# VREG_AOZ1021AI_3V3_3A.net
KiCad netlist of a schematic drawn in Altium Designer
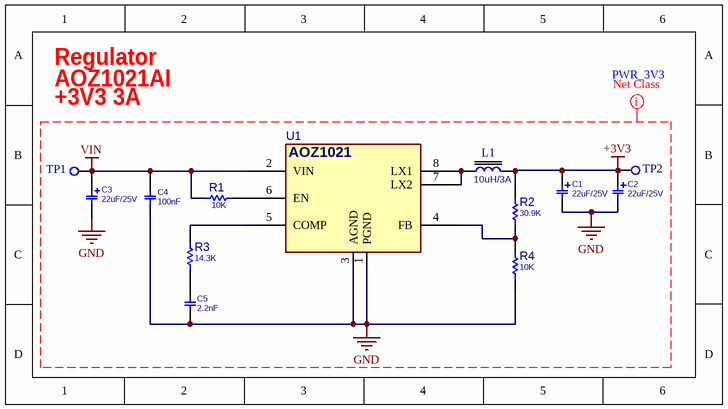
[diagram p0: VREG AOZ1021AI +3V3 3A.SchDoc]

(export (version "E")
  (design (tool "Eeschema 10.0.6"))
  (components
    (comp (ref "C1")
      (value "22uF/25V")
      (footprint "C_TN_A")
      (description "CAP, SMD, TAN")
      (libsource (lib "Passive") (part "CAP_SMD_TAN"))
    )
    (comp (ref "C2")
      (value "22uF/25V")
      (footprint "C_TN_A")
      (description "CAP, SMD, TAN")
      (libsource (lib "Passive") (part "CAP_SMD_TAN"))
    )
    (comp (ref "C3")
      (value "22uF/25V")
      (footprint "C_TN_A")
      (description "CAP, SMD, TAN")
      (libsource (lib "Passive") (part "CAP_SMD_TAN"))
    )
    (comp (ref "C4")
      (value "100nF")
      (footprint "C0603S")
      (description "CAP, SMD, MLCC")
      (fields (field (name "MANF_P#") "MANF_PART#") (field (name "MANF") "Murata"))
      (libsource (lib "Passive") (part "CAP_SMD_MLCC"))
    )
    (comp (ref "C5")
      (value "2.2nF")
      (footprint "C0603S")
      (description "CAP, SMD, MLCC")
      (fields (field (name "MANF_P#") "MANF_PART#") (field (name "MANF") "Murata"))
      (libsource (lib "Passive") (part "CAP_SMD_MLCC"))
    )
    (comp (ref "L1")
      (value "10uH/3A")
      (footprint "L_8X8")
      (description "IND, PWR, SMD")
      (libsource (lib "Passive") (part "INDPWR_SMD"))
    )
    (comp (ref "R1")
      (value "10K")
      (footprint "R0603S")
      (description "RES, SMD")
      (fields (field (name "MANF_P#") "RK73H1ETTP4701F") (field (name "MANF") "KOA SPEER"))
      (libsource (lib "Passive") (part "RES_SMD"))
    )
    (comp (ref "R2")
      (value "30.9K")
      (footprint "R0603S")
      (description "RES, SMD")
      (fields (field (name "MANF_P#") "RK73H1ETTP4701F") (field (name "MANF") "KOA SPEER"))
      (libsource (lib "Passive") (part "RES_SMD"))
    )
    (comp (ref "R3")
      (value "14.3K")
      (footprint "R0603S")
      (description "RES, SMD")
      (fields (field (name "MANF_P#") "RK73H1ETTP4701F") (field (name "MANF") "KOA SPEER"))
      (libsource (lib "Passive") (part "RES_SMD"))
    )
    (comp (ref "R4")
      (value "10K")
      (footprint "R0603S")
      (description "RES, SMD")
      (fields (field (name "MANF_P#") "RK73H1ETTP4701F") (field (name "MANF") "KOA SPEER"))
      (libsource (lib "Passive") (part "RES_SMD"))
    )
    (comp (ref "TP1")
      (value "Test Point")
      (footprint "TPSMD_C1")
      (libsource (lib "PW Components") (part "Test Point"))
    )
    (comp (ref "TP2")
      (value "Test Point")
      (footprint "TPSMD_C1")
      (libsource (lib "PW Components") (part "Test Point"))
    )
    (comp (ref "U1")
      (value "AOZ1021AI")
      (footprint "SO_8")
      (description "REG, Switching, Buck, 3A, ADJ, 500KHz, 4.5~16VIN, SO-8")
      (fields (field (name "MANF") "AOSMD"))
      (libsource (lib "PW Components") (part "VREG_AOZ1021AI_SO8"))
    )
  )
  (nets
    (net (code "1") (name "+3V3") (class "Default")
      (node (ref "C1") (pin "1") (pinfunction "1_1") (pintype "passive"))
      (node (ref "C2") (pin "1") (pinfunction "1_1") (pintype "passive"))
      (node (ref "L1") (pin "2") (pinfunction "2_2") (pintype "passive"))
      (node (ref "R2") (pin "1") (pinfunction "1_1") (pintype "passive"))
      (node (ref "TP2") (pin "1") (pinfunction "TP_1") (pintype "passive"))
    )
    (net (code "2") (name "GND") (class "Default")
      (node (ref "C1") (pin "2") (pinfunction "2_2") (pintype "passive"))
      (node (ref "C2") (pin "2") (pinfunction "2_2") (pintype "passive"))
      (node (ref "C3") (pin "2") (pinfunction "2_2") (pintype "passive"))
      (node (ref "C4") (pin "1") (pinfunction "1_1") (pintype "passive"))
      (node (ref "C5") (pin "1") (pinfunction "1_1") (pintype "passive"))
      (node (ref "R4") (pin "2") (pinfunction "2_2") (pintype "passive"))
      (node (ref "U1") (pin "1") (pinfunction "PGND_1") (pintype "power_in"))
      (node (ref "U1") (pin "3") (pinfunction "AGND_3") (pintype "power_in"))
    )
    (net (code "3") (name "Net-(C5-Pad2)") (class "Default")
      (node (ref "C5") (pin "2") (pinfunction "2_2") (pintype "passive"))
      (node (ref "R3") (pin "2") (pinfunction "2_2") (pintype "passive"))
    )
    (net (code "4") (name "Net-(U1-COMP)") (class "Default")
      (node (ref "R3") (pin "1") (pinfunction "1_1") (pintype "passive"))
      (node (ref "U1") (pin "5") (pinfunction "COMP_5") (pintype "passive"))
    )
    (net (code "5") (name "Net-(U1-EN)") (class "Default")
      (node (ref "R1") (pin "1") (pinfunction "1_1") (pintype "passive"))
      (node (ref "U1") (pin "6") (pinfunction "EN_6") (pintype "passive"))
    )
    (net (code "6") (name "Net-(U1-FB)") (class "Default")
      (node (ref "R2") (pin "2") (pinfunction "2_2") (pintype "passive"))
      (node (ref "R4") (pin "1") (pinfunction "1_1") (pintype "passive"))
      (node (ref "U1") (pin "4") (pinfunction "FB_4") (pintype "passive"))
    )
    (net (code "7") (name "Net-(U1-LX1)") (class "Default")
      (node (ref "L1") (pin "1") (pinfunction "1_1") (pintype "passive"))
      (node (ref "U1") (pin "7") (pinfunction "LX2_7") (pintype "passive"))
      (node (ref "U1") (pin "8") (pinfunction "LX1_8") (pintype "passive"))
    )
    (net (code "8") (name "VIN") (class "Default")
      (node (ref "C3") (pin "1") (pinfunction "1_1") (pintype "passive"))
      (node (ref "C4") (pin "2") (pinfunction "2_2") (pintype "passive"))
      (node (ref "R1") (pin "2") (pinfunction "2_2") (pintype "passive"))
      (node (ref "TP1") (pin "1") (pinfunction "TP_1") (pintype "passive"))
      (node (ref "U1") (pin "2") (pinfunction "VIN_2") (pintype "power_in"))
    )
  )
)
